# Sheet1.net
KiCad netlist of a schematic drawn in Altium Designer
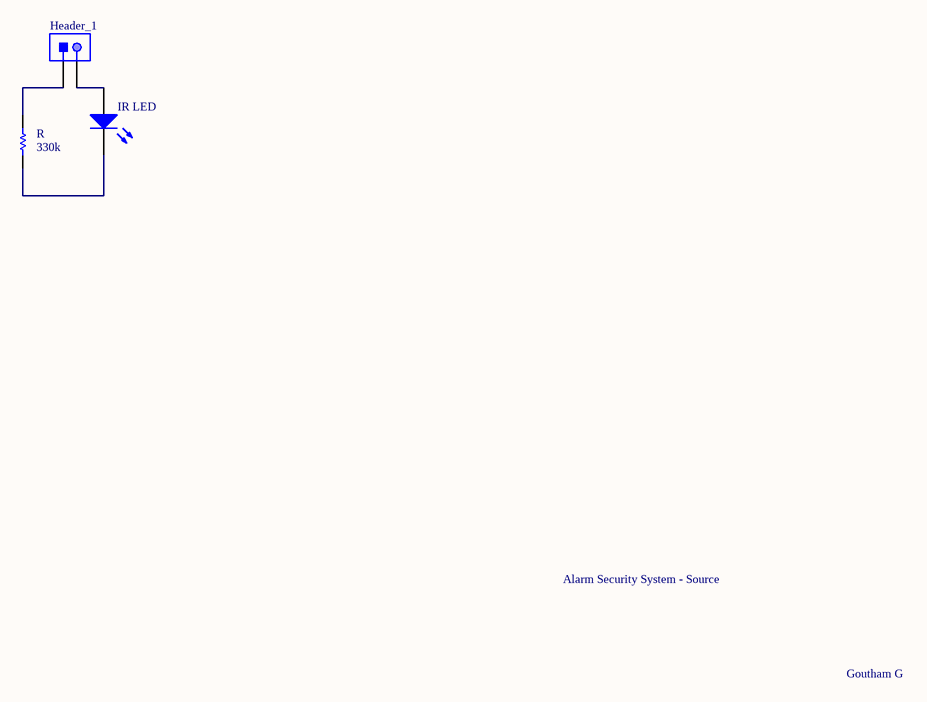
[diagram p0: Sheet1.SchDoc]

(export (version "E")
  (design (tool "Eeschema 10.0.6"))
  (components
    (comp (ref "Header_1")
      (value "B2P-VH(LF)(SN)")
      (footprint "JST-B2P-VH(LF)(SN)_V")
      (fields (field (name "MANUFACTURER") "JST"))
      (libsource (lib "GOUTHAM GANESH KUMAR") (part "CN-1P-M-R2"))
    )
    (comp (ref "IR LED")
      (value "TSAL6200")
      (footprint "VISH-TSAL6200")
      (fields (field (name "MANUFACTURER") "Vishay"))
      (libsource (lib "Altium Content Vault") (part "LED-AK-2"))
    )
    (comp (ref "R")
      (value "Resistor 330k +/-1% 0805 125 mW")
      (footprint "RESC2013X70X40ML20T20")
      (description "Chip Resistor, 330 KOhm, +/- 1%, 0.125 W, -55 to 155 degC, 0805 (2013 Metric)")
      (fields (field (name "TOLERANCE") "1%") (field (name "POWER") "125mW") (field (name "R") "330k"))
      (libsource (lib "GOUTHAM GANESH KUMAR") (part "RES-2"))
    )
  )
  (nets
    (net (code "1") (name "Net-(Header_1-Pad1)") (class "Default")
      (node (ref "Header_1") (pin "1") (pinfunction "1_1") (pintype "passive"))
      (node (ref "R") (pin "2") (pinfunction "2_2") (pintype "passive"))
    )
    (net (code "2") (name "Net-(IR LED-A)") (class "Default")
      (node (ref "Header_1") (pin "2") (pinfunction "2_2") (pintype "passive"))
      (node (ref "IR LED") (pin "1") (pinfunction "A_1") (pintype "passive"))
    )
    (net (code "3") (name "Net-(IR LED-K)") (class "Default")
      (node (ref "IR LED") (pin "2") (pinfunction "K_2") (pintype "passive"))
      (node (ref "R") (pin "1") (pinfunction "1_1") (pintype "passive"))
    )
  )
)
